# 12V_PWR.net
KiCad netlist of a schematic drawn in Altium Designer
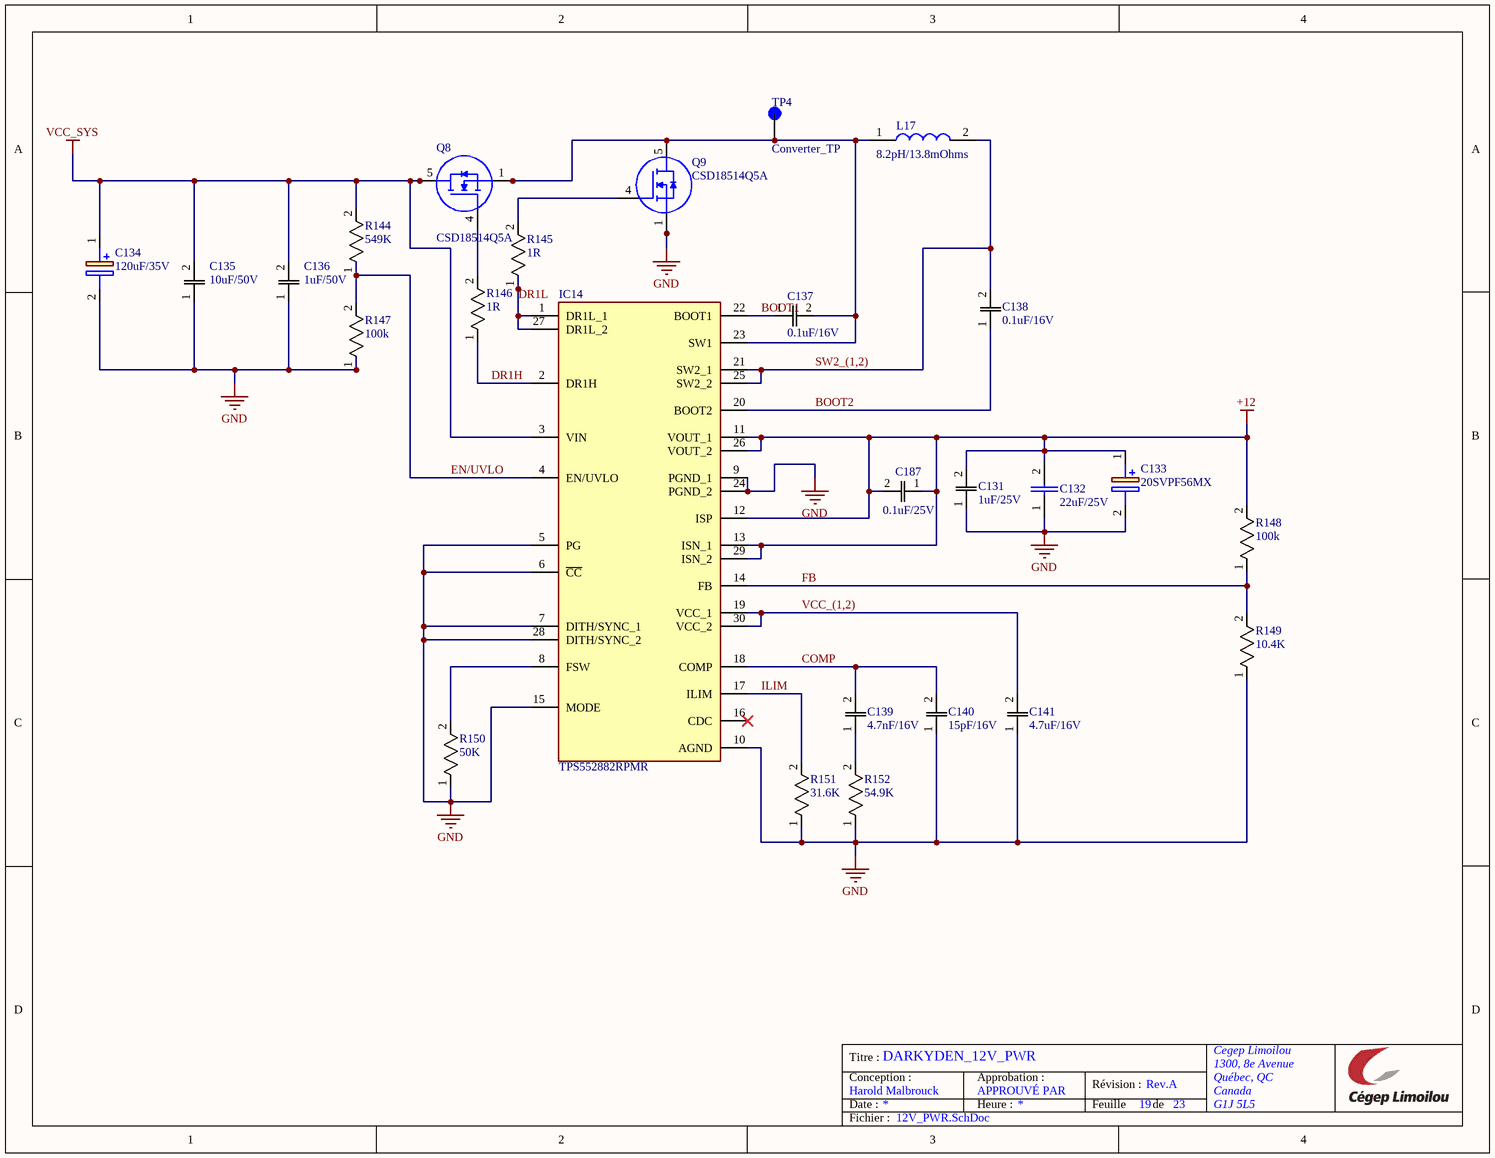
[diagram p0: 12V_PWR.SchDoc]

(export (version "E")
  (design (tool "Eeschema 10.0.6"))
  (components
    (comp (ref "C131")
      (value "1uF/25V")
      (footprint "C0805")
      (description "1 µF, 25 V (DC), ±10 %, SMD 0805, X7R, C0805C105K3RAC7800")
      (fields
        (field (name "MANUFACTURER_PART_NUMBER") "C0805C105K3RACTU")
        (field (name "MOUSER PART NUMBER") "80-C0805C105K3R")
      )
      (libsource (lib "DARKYDEN") (part "C0805C105K3RACTU"))
    )
    (comp (ref "C132")
      (value "22uF/25V")
      (footprint "SamacSys:CAPC3225X270N")
      (description "1210 22 uF 25 V ±10% Tolerance X5R SMT Multilayer Ceramic Capacitor")
      (fields
        (field (name "MANUFACTURER_PART_NUMBER") "GRM32ER61E226KE15L")
        (field (name "MOUSER PART NUMBER") "81-GRM32ER61E226KE15")
      )
      (libsource (lib "SamacSys") (part "GRM32ER61E226KE15L"))
    )
    (comp (ref "C133")
      (value "20SVPF56MX")
      (footprint "SamacSys:16SVF82M")
      (description "56uF 20VDC 20%( Cap Aluminum Polymer SMD 0.03 Ohm 2800mA 5000h 105C T/R")
      (fields (field (name "MOUSER PART NUMBER") "667-20SVPF56MX") (field (name "MANUFACTURER") "Panasonic"))
      (libsource (lib "SamacSys") (part "20SVPF56MX"))
    )
    (comp (ref "C134")
      (value "120uF/35V")
      (footprint "SamacSys:16SVF1000M")
      (description "120uF 35VDC 20% Cap Aluminum Polymer   SMD 0.018 Ohm 4400mA 5000h 105C T/R")
      (fields
        (field (name "MANUFACTURER_PART_NUMBER") "35SVPF120M")
        (field (name "MOUSER PART NUMBER") "667-35SVPF120M")
      )
      (libsource (lib "SamacSys") (part "35SVPF120M"))
    )
    (comp (ref "C135")
      (value "10uF/50V")
      (footprint "SamacSys:CAPC3225X230N")
      (description "10 uF 50 V 1210 ±20 % Tolerance X7R SMT Multilayer Ceramic Capacitor")
      (fields
        (field (name "MANUFACTURER_PART_NUMBER") "C3225X7R1H106M250AC")
        (field (name "MOUSER PART NUMBER") "810-C3225X7R1H106MAC")
      )
      (libsource (lib "SamacSys") (part "C3225X7R1H106M250AC"))
    )
    (comp (ref "C136")
      (value "1uF/50V")
      (footprint "SamacSys:CAPC1608X80N")
      (description "1uF / 50 V, X5R,  Surface Mount, 0603")
      (fields
        (field (name "MANUFACTURER_PART_NUMBER") "C1608X5R1H105K080AB")
        (field (name "MOUSER PART NUMBER") "810-C1608X5R1H105K")
      )
      (libsource (lib "SamacSys") (part "C1608X5R1H105K080AB"))
    )
    (comp (ref "C137")
      (value "0.1uF/16V")
      (footprint "C0805")
      (description "0.1uF/16V ±10% X7R 0805 (2012METRIC) Ceramic Capacitor SMD Auto X7R")
      (fields
        (field (name "MANUFACTURER") "KEMET")
        (field (name "MANUFACTURER PART NUMBER") "C0805C104K4RACAUTO")
      )
      (libsource (lib "DARKYDEN") (part "C0805C104K4RACAUTO"))
    )
    (comp (ref "C138")
      (value "0.1uF/16V")
      (footprint "C0805")
      (description "0.1uF/16V ±10% X7R 0805 (2012METRIC) Ceramic Capacitor SMD Auto X7R")
      (fields
        (field (name "MANUFACTURER") "KEMET")
        (field (name "MANUFACTURER PART NUMBER") "C0805C104K4RACAUTO")
      )
      (libsource (lib "DARKYDEN") (part "C0805C104K4RACAUTO"))
    )
    (comp (ref "C139")
      (value "4.7nF/16V")
      (footprint "c0805")
      (description "4.7nF, 16VDC, 10-% Tol, 10+% Tol, X7R-TC Code, -15, 15%-TC RoHS Compliant: Yes")
      (fields
        (field (name "MANUFACTURER") "KEMET")
        (field (name "MANUFACTURER PART NUMBER") "C0805C472K4RACTU")
      )
      (libsource (lib "DARKYDEN") (part "C0805C472K4RACTU"))
    )
    (comp (ref "C140")
      (value "15pF/16V")
      (footprint "C0805")
      (description "15 pF, 16 V, ± 10%, C0G (NP0), 0805 [2012 Metric]")
      (fields
        (field (name "MANUFACTURER") "KEMET")
        (field (name "MANUFACTURER PART NUMBER") "C0805C150K4GACTU")
      )
      (libsource (lib "DARKYDEN") (part "C0805C150K4GACTU"))
    )
    (comp (ref "C141")
      (value "4.7uF/16V")
      (footprint "C0805")
      (description "4.7 uF, 16 V, ± 10%, X7R, 0805 [2012 Metric]")
      (fields
        (field (name "MANUFACTURER_PART_NUMBER") "C0805C475K4RACTU")
        (field (name "MOUSER PART NUMBER") "80-C0805C475K4R")
      )
      (libsource (lib "DARKYDEN") (part "C0805C475K4RACTU"))
    )
    (comp (ref "C187")
      (value "0.1uF/25V")
      (footprint "c0805")
      (description "0.1uF 25V X7R 10% SMD 0805 125C Plastic T/R")
      (fields
        (field (name "MANUFACTURER") "KEMET")
        (field (name "MANUFACTURER PART NUMBER") "C0805C104K3RACTU")
      )
      (libsource (lib "DARKYDEN") (part "C0805C104K3RACTU"))
    )
    (comp (ref "IC14")
      (value "TPS552882RPMR")
      (footprint "SamacSys:TPS552882RPMR")
      (description "36-V, 16-A buck-boost converter 26-VQFN-HR -40 to 125")
      (fields
        (field (name "MOUSER PART NUMBER") "595-TPS552882RPMR")
        (field (name "MANUFACTURER") "Texas Instruments")
      )
      (libsource (lib "SamacSys") (part "TPS552882RPMR"))
    )
    (comp (ref "L17")
      (value "8.2pH/13.8mOhms")
      (footprint "SamacSys:INDPM135126X650N")
      (description "Inductor Power Shielded/Molded Wirewound 8.2uH 20% 100KHz 15A 0.0138Ohm DCR Automotive T/R")
      (fields
        (field (name "MANUFACTURER_PART_NUMBER") "PA4343.822ANLT")
        (field (name "MOUSER PART NUMBER") "673-PA4343.822ANLT")
      )
      (libsource (lib "SamacSys") (part "PA4343.822ANLT"))
    )
    (comp (ref "Q8")
      (value "CSD18514Q5A")
      (footprint "SamacSys:CSD18514Q5A")
      (description "MOSFET N-Channel 40 V 89A (Tc) 74W (Tc) Surface Mount 8-VSONP (5x6)")
      (fields (field (name "MOUSER PART NUMBER") "595-CSD18514Q5A"))
      (libsource (lib "SamacSys") (part "CSD18514Q5A"))
    )
    (comp (ref "Q9")
      (value "CSD18514Q5A")
      (footprint "SamacSys:CSD18514Q5A")
      (description "MOSFET N-Channel 40 V 89A (Tc) 74W (Tc) Surface Mount 8-VSONP (5x6)")
      (fields (field (name "MOUSER PART NUMBER") "595-CSD18514Q5A"))
      (libsource (lib "SamacSys") (part "CSD18514Q5A"))
    )
    (comp (ref "R144")
      (value "549K")
      (footprint "RESC1608X55N")
      (description "549 kOhm, ± 1%, 100 mW, 0603 [1608 Metric], Thick Film, Precision")
      (fields
        (field (name "MANUFACTURER") "Panasonic")
        (field (name "MANUFACTURER PART NUMBER") "ERJ-3EKF5493V")
      )
      (libsource (lib "DARKYDEN") (part "ERJ-3EKF5493V"))
    )
    (comp (ref "R145")
      (value "1R")
      (footprint "SamacSys:RESC1608X55N")
      (description "1 Ohm 5% 1/10W  Res Thick Film 0603 -100ppm/¦")
      (fields
        (field (name "MANUFACTURER_PART_NUMBER") "ERJ-3GEYJ1R0V")
        (field (name "MOUSER PART NUMBER") "667-ERJ-3GEYJ1R0V")
      )
      (libsource (lib "DARKYDEN") (part "ERJ-3GEYJ1R0V"))
    )
    (comp (ref "R146")
      (value "1R")
      (footprint "SamacSys:RESC1608X55N")
      (description "1 Ohm 5% 1/10W  Res Thick Film 0603 -100ppm/¦")
      (fields
        (field (name "MANUFACTURER_PART_NUMBER") "ERJ-3GEYJ1R0V")
        (field (name "MOUSER PART NUMBER") "667-ERJ-3GEYJ1R0V")
      )
      (libsource (lib "DARKYDEN") (part "ERJ-3GEYJ1R0V"))
    )
    (comp (ref "R147")
      (value "100k")
      (footprint "SamacSys:RESC1608X55N")
      (description "100K Ohm 5%  Res Thick Film 0603 1/10W +/-200ppm/ßC Molded SMD Punched Carrier T/R")
      (fields
        (field (name "MANUFACTURER_PART_NUMBER") "ERJ-3GEYJ104V")
        (field (name "MOUSER PART NUMBER") "667-ERJ-3GEYJ104V")
      )
      (libsource (lib "DARKYDEN") (part "ERJ-3GEYJ104V"))
    )
    (comp (ref "R148")
      (value "100k")
      (footprint "SamacSys:RESC1608X55N")
      (description "100K Ohm 5%  Res Thick Film 0603 1/10W +/-200ppm/ßC Molded SMD Punched Carrier T/R")
      (fields
        (field (name "MANUFACTURER_PART_NUMBER") "ERJ-3GEYJ104V")
        (field (name "MOUSER PART NUMBER") "667-ERJ-3GEYJ104V")
      )
      (libsource (lib "DARKYDEN") (part "ERJ-3GEYJ104V"))
    )
    (comp (ref "R149")
      (value "10.4K")
      (footprint "RESC1608X55N")
      (description "10.4kOhm 0.1% High Precision-High Stability Chip Resistor Thin Film 0603  Paper T/R")
      (fields (field (name "MP") "RT0603BRD0710K4L") (field (name "MANUFACTURER") "Yageo"))
      (libsource (lib "DARKYDEN") (part "RT0603BRD0710K4L"))
    )
    (comp (ref "R150")
      (value "50K")
      (footprint "SamacSys:RESC1005X40N")
      (description "50 kΩ  Tolerance: 1.0%  Power: 63 mW  Package:0402")
      (fields
        (field (name "MANUFACTURER_PART_NUMBER") "CRCW040250K0FKED")
        (field (name "MOUSER PART NUMBER") "71-CRCW0402-50K-E3")
      )
      (libsource (lib "SamacSys") (part "CRCW040250K0FKED"))
    )
    (comp (ref "R151")
      (value "31.6K")
      (footprint "SamacSys:RESC1005X40N")
      (description "31.6 kΩ  Tolerance: 1.0%  Power: 63 mW")
      (fields
        (field (name "MANUFACTURER_PART_NUMBER") "CRCW040231K6FKED")
        (field (name "MOUSER PART NUMBER") "71-CRCW0402-31.6K-E3")
      )
      (libsource (lib "SamacSys") (part "CRCW040231K6FKED"))
    )
    (comp (ref "R152")
      (value "54.9K")
      (footprint "SamacSys:RESC1005X40N")
      (description "54.9 kΩ  Tolerance: 1.0%  Power: 63 mW  PAckage:0402")
      (fields
        (field (name "MANUFACTURER_PART_NUMBER") "CRCW040254K9FKED")
        (field (name "MOUSER PART NUMBER") "71-CRCW0402-54.9K-E3")
      )
      (libsource (lib "SamacSys") (part "CRCW040254K9FKED"))
    )
    (comp (ref "TP4")
      (value "Converter_TP")
      (footprint "KEYSTONE_5006")
      (description "Test Point Compact THM PC .350 L .125 OD Heat Resistant Nylon 46 Black ¦ Keystone Electronics 5006")
      (fields (field (name "MF") "Keystone Electronics Corp.") (field (name "MP") "5006"))
      (libsource (lib "test_point") (part "5006"))
    )
  )
  (nets
    (net (code "1") (name "+12") (class "Default")
      (node (ref "C131") (pin "2") (pinfunction "2_2") (pintype "passive"))
      (node (ref "C132") (pin "2") (pinfunction "2_2") (pintype "passive"))
      (node (ref "C133") (pin "1") (pinfunction "+_1") (pintype "passive"))
      (node (ref "C187") (pin "1") (pinfunction "1_1") (pintype "passive"))
      (node (ref "C187") (pin "2") (pinfunction "2_2") (pintype "passive"))
      (node (ref "IC14") (pin "11") (pinfunction "VOUT_1_11") (pintype "passive"))
      (node (ref "IC14") (pin "12") (pinfunction "ISP_12") (pintype "passive"))
      (node (ref "IC14") (pin "13") (pinfunction "ISN_1_13") (pintype "passive"))
      (node (ref "IC14") (pin "26") (pinfunction "VOUT_2_26") (pintype "passive"))
      (node (ref "IC14") (pin "29") (pinfunction "ISN_2_29") (pintype "passive"))
      (node (ref "R148") (pin "2") (pinfunction "2_2") (pintype "passive"))
    )
    (net (code "2") (name "/BOOT1") (class "Default")
      (node (ref "C137") (pin "1") (pinfunction "1_1") (pintype "passive"))
      (node (ref "IC14") (pin "22") (pinfunction "BOOT1_22") (pintype "passive"))
    )
    (net (code "3") (name "/BOOT2") (class "Default")
      (node (ref "C138") (pin "1") (pinfunction "1_1") (pintype "passive"))
      (node (ref "IC14") (pin "20") (pinfunction "BOOT2_20") (pintype "passive"))
    )
    (net (code "4") (name "/COMP") (class "Default")
      (node (ref "C139") (pin "2") (pinfunction "2_2") (pintype "passive"))
      (node (ref "C140") (pin "2") (pinfunction "2_2") (pintype "passive"))
      (node (ref "IC14") (pin "18") (pinfunction "COMP_18") (pintype "passive"))
    )
    (net (code "5") (name "/DR1H") (class "Default")
      (node (ref "IC14") (pin "2") (pinfunction "DR1H_2") (pintype "passive"))
      (node (ref "R146") (pin "1") (pinfunction "1_1") (pintype "passive"))
    )
    (net (code "6") (name "/DR1L") (class "Default")
      (node (ref "IC14") (pin "1") (pinfunction "DR1L_1_1") (pintype "passive"))
      (node (ref "IC14") (pin "27") (pinfunction "DR1L_2_27") (pintype "passive"))
      (node (ref "R145") (pin "1") (pinfunction "1_1") (pintype "passive"))
    )
    (net (code "7") (name "/EN{slash}UVLO") (class "Default")
      (node (ref "IC14") (pin "4") (pinfunction "EN/UVLO_4") (pintype "passive"))
      (node (ref "R144") (pin "1") (pinfunction "1_1") (pintype "passive"))
      (node (ref "R147") (pin "2") (pinfunction "2_2") (pintype "passive"))
    )
    (net (code "8") (name "/FB") (class "Default")
      (node (ref "IC14") (pin "14") (pinfunction "FB_14") (pintype "passive"))
      (node (ref "R148") (pin "1") (pinfunction "1_1") (pintype "passive"))
      (node (ref "R149") (pin "2") (pinfunction "2_2") (pintype "passive"))
    )
    (net (code "9") (name "/ILIM") (class "Default")
      (node (ref "IC14") (pin "17") (pinfunction "ILIM_17") (pintype "passive"))
      (node (ref "R151") (pin "2") (pinfunction "2_2") (pintype "passive"))
    )
    (net (code "10") (name "/SW2_(1,2)") (class "Default")
      (node (ref "C138") (pin "2") (pinfunction "2_2") (pintype "passive"))
      (node (ref "IC14") (pin "21") (pinfunction "SW2_1_21") (pintype "passive"))
      (node (ref "IC14") (pin "25") (pinfunction "SW2_2_25") (pintype "passive"))
      (node (ref "L17") (pin "2") (pinfunction "2_2") (pintype "passive"))
    )
    (net (code "11") (name "/VCC_(1,2)") (class "Default")
      (node (ref "C141") (pin "2") (pinfunction "2_2") (pintype "passive"))
      (node (ref "IC14") (pin "19") (pinfunction "VCC_1_19") (pintype "passive"))
      (node (ref "IC14") (pin "30") (pinfunction "VCC_2_30") (pintype "passive"))
    )
    (net (code "12") (name "GND") (class "Default")
      (node (ref "C131") (pin "1") (pinfunction "1_1") (pintype "passive"))
      (node (ref "C132") (pin "1") (pinfunction "1_1") (pintype "passive"))
      (node (ref "C133") (pin "2") (pinfunction "-_2") (pintype "passive"))
      (node (ref "C134") (pin "2") (pinfunction "-_2") (pintype "passive"))
      (node (ref "C135") (pin "1") (pinfunction "1_1") (pintype "passive"))
      (node (ref "C136") (pin "1") (pinfunction "1_1") (pintype "passive"))
      (node (ref "C140") (pin "1") (pinfunction "1_1") (pintype "passive"))
      (node (ref "C141") (pin "1") (pinfunction "1_1") (pintype "passive"))
      (node (ref "IC14") (pin "10") (pinfunction "AGND_10") (pintype "passive"))
      (node (ref "IC14") (pin "15") (pinfunction "MODE_15") (pintype "passive"))
      (node (ref "IC14") (pin "24") (pinfunction "PGND_2_24") (pintype "passive"))
      (node (ref "IC14") (pin "28") (pinfunction "DITH/SYNC_2_28") (pintype "passive"))
      (node (ref "IC14") (pin "5") (pinfunction "PG_5") (pintype "passive"))
      (node (ref "IC14") (pin "6") (pinfunction "~{CC}_6") (pintype "passive"))
      (node (ref "IC14") (pin "7") (pinfunction "DITH/SYNC_1_7") (pintype "passive"))
      (node (ref "IC14") (pin "9") (pinfunction "PGND_1_9") (pintype "passive"))
      (node (ref "Q9") (pin "1") (pinfunction "S_1") (pintype "passive"))
      (node (ref "Q9") (pin "2") (pinfunction "S_2_2") (pintype "passive"))
      (node (ref "Q9") (pin "3") (pinfunction "S_3_3") (pintype "passive"))
      (node (ref "R147") (pin "1") (pinfunction "1_1") (pintype "passive"))
      (node (ref "R149") (pin "1") (pinfunction "1_1") (pintype "passive"))
      (node (ref "R150") (pin "1") (pinfunction "1_1") (pintype "passive"))
      (node (ref "R151") (pin "1") (pinfunction "1_1") (pintype "passive"))
      (node (ref "R152") (pin "1") (pinfunction "1_1") (pintype "passive"))
    )
    (net (code "13") (name "Net-(C139-Pad1)") (class "Default")
      (node (ref "C139") (pin "1") (pinfunction "1_1") (pintype "passive"))
      (node (ref "R152") (pin "2") (pinfunction "2_2") (pintype "passive"))
    )
    (net (code "14") (name "Net-(IC14-FSW)") (class "Default")
      (node (ref "IC14") (pin "8") (pinfunction "FSW_8") (pintype "passive"))
      (node (ref "R150") (pin "2") (pinfunction "2_2") (pintype "passive"))
    )
    (net (code "15") (name "Net-(IC14-SW1)") (class "Default")
      (node (ref "C137") (pin "2") (pinfunction "2_2") (pintype "passive"))
      (node (ref "IC14") (pin "23") (pinfunction "SW1_23") (pintype "passive"))
      (node (ref "L17") (pin "1") (pinfunction "1_1") (pintype "passive"))
      (node (ref "Q8") (pin "1") (pinfunction "S_1") (pintype "passive"))
      (node (ref "Q8") (pin "2") (pinfunction "S_2_2") (pintype "passive"))
      (node (ref "Q8") (pin "3") (pinfunction "S_3_3") (pintype "passive"))
      (node (ref "Q9") (pin "5") (pinfunction "D_5") (pintype "passive"))
      (node (ref "Q9") (pin "6") (pinfunction "D_2_6") (pintype "passive"))
      (node (ref "Q9") (pin "7") (pinfunction "D_3_7") (pintype "passive"))
      (node (ref "Q9") (pin "8") (pinfunction "D_4_8") (pintype "passive"))
      (node (ref "Q9") (pin "9") (pinfunction "D_5_9") (pintype "passive"))
      (node (ref "TP4") (pin "TP") (pinfunction "TP_TP") (pintype "passive"))
    )
    (net (code "16") (name "Net-(Q8-G)") (class "Default")
      (node (ref "Q8") (pin "4") (pinfunction "G_4") (pintype "passive"))
      (node (ref "R146") (pin "2") (pinfunction "2_2") (pintype "passive"))
    )
    (net (code "17") (name "Net-(Q9-G)") (class "Default")
      (node (ref "Q9") (pin "4") (pinfunction "G_4") (pintype "passive"))
      (node (ref "R145") (pin "2") (pinfunction "2_2") (pintype "passive"))
    )
    (net (code "18") (name "VCC_SYS") (class "Default")
      (node (ref "C134") (pin "1") (pinfunction "+_1") (pintype "passive"))
      (node (ref "C135") (pin "2") (pinfunction "2_2") (pintype "passive"))
      (node (ref "C136") (pin "2") (pinfunction "2_2") (pintype "passive"))
      (node (ref "IC14") (pin "3") (pinfunction "VIN_3") (pintype "passive"))
      (node (ref "Q8") (pin "5") (pinfunction "D_5") (pintype "passive"))
      (node (ref "Q8") (pin "6") (pinfunction "D_2_6") (pintype "passive"))
      (node (ref "Q8") (pin "7") (pinfunction "D_3_7") (pintype "passive"))
      (node (ref "Q8") (pin "8") (pinfunction "D_4_8") (pintype "passive"))
      (node (ref "Q8") (pin "9") (pinfunction "D_5_9") (pintype "passive"))
      (node (ref "R144") (pin "2") (pinfunction "2_2") (pintype "passive"))
    )
    (net (code "19") (name "unconnected-(IC14-CDC-Pad16)") (class "Default")
      (node (ref "IC14") (pin "16") (pinfunction "CDC_16") (pintype "passive+no_connect"))
    )
  )
)
